# light_pcb.net
KiCad netlist of a schematic drawn in EAGLE
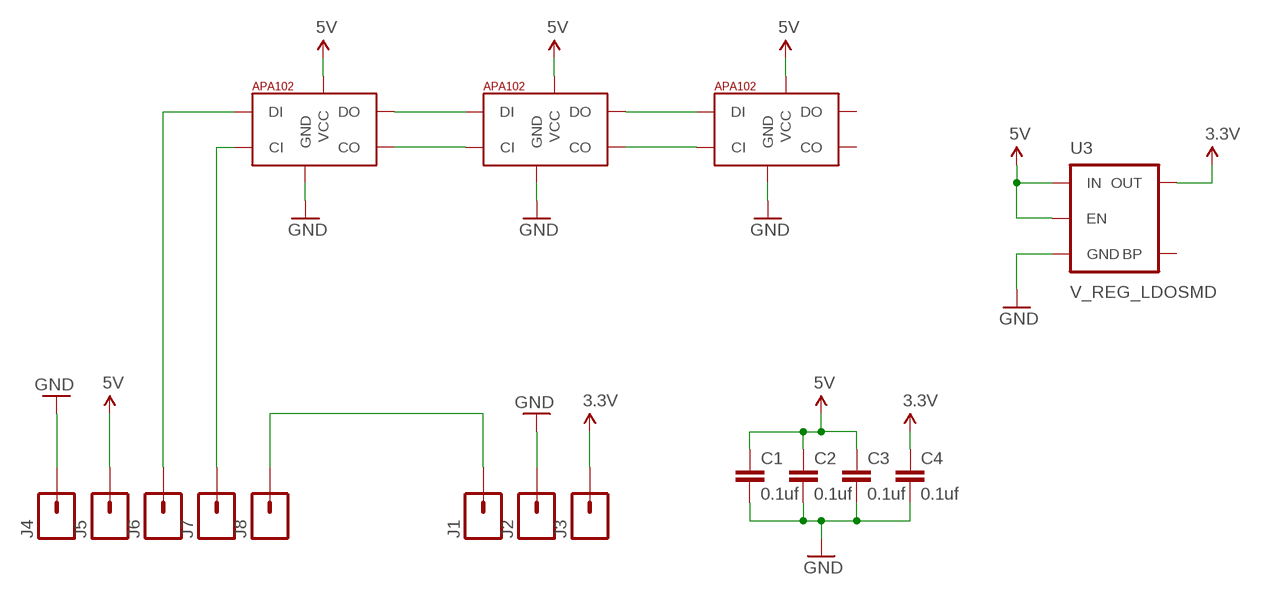
[diagram p0: schematic, sheet 1]

(export (version "E")
  (design (tool "Eeschema 10.0.6"))
  (components
    (comp (ref "C1")
      (value "0.1uf")
      (footprint "eagle-import:0805")
      (libsource (lib "eagle-import") (part "CAP0805"))
    )
    (comp (ref "C2")
      (value "0.1uf")
      (footprint "eagle-import:0805")
      (libsource (lib "eagle-import") (part "CAP0805"))
    )
    (comp (ref "C3")
      (value "0.1uf")
      (footprint "eagle-import:0805")
      (libsource (lib "eagle-import") (part "CAP0805"))
    )
    (comp (ref "C4")
      (value "0.1uf")
      (footprint "eagle-import:0805")
      (libsource (lib "eagle-import") (part "CAP0805"))
    )
    (comp (ref "J1")
      (value "M01SMD-4.5X1.5")
      (footprint "eagle-import:PAD-1.5X4.5")
      (libsource (lib "eagle-import") (part "M01SMD-4.5X1.5"))
    )
    (comp (ref "J2")
      (value "M01SMD-4.5X1.5")
      (footprint "eagle-import:PAD-1.5X4.5")
      (libsource (lib "eagle-import") (part "M01SMD-4.5X1.5"))
    )
    (comp (ref "J3")
      (value "M01SMD-4.5X1.5")
      (footprint "eagle-import:PAD-1.5X4.5")
      (libsource (lib "eagle-import") (part "M01SMD-4.5X1.5"))
    )
    (comp (ref "J4")
      (value "M01SMD-4.5X1.5")
      (footprint "eagle-import:PAD-1.5X4.5")
      (libsource (lib "eagle-import") (part "M01SMD-4.5X1.5"))
    )
    (comp (ref "J5")
      (value "M01SMD-4.5X1.5")
      (footprint "eagle-import:PAD-1.5X4.5")
      (libsource (lib "eagle-import") (part "M01SMD-4.5X1.5"))
    )
    (comp (ref "J6")
      (value "M01SMD-4.5X1.5")
      (footprint "eagle-import:PAD-1.5X4.5")
      (libsource (lib "eagle-import") (part "M01SMD-4.5X1.5"))
    )
    (comp (ref "J7")
      (value "M01SMD-4.5X1.5")
      (footprint "eagle-import:PAD-1.5X4.5")
      (libsource (lib "eagle-import") (part "M01SMD-4.5X1.5"))
    )
    (comp (ref "J8")
      (value "M01SMD-4.5X1.5")
      (footprint "eagle-import:PAD-1.5X4.5")
      (libsource (lib "eagle-import") (part "M01SMD-4.5X1.5"))
    )
    (comp (ref "U$1")
      (value "APA1025050")
      (footprint "eagle-import:APA102_5050")
      (libsource (lib "eagle-import") (part "APA1025050"))
    )
    (comp (ref "U$2")
      (value "APA1025050")
      (footprint "eagle-import:APA102_5050")
      (libsource (lib "eagle-import") (part "APA1025050"))
    )
    (comp (ref "U$3")
      (value "APA1025050")
      (footprint "eagle-import:APA102_5050")
      (libsource (lib "eagle-import") (part "APA1025050"))
    )
    (comp (ref "U3")
      (value "V_REG_LDOSMD")
      (footprint "eagle-import:SOT23-5")
      (libsource (lib "eagle-import") (part "V_REG_LDOSMD"))
    )
  )
  (nets
    (net (code "1") (name "3.3V") (class "Default")
      (node (ref "C4") (pin "1") (pinfunction "1_1") (pintype "passive"))
      (node (ref "J3") (pin "P$1") (pinfunction "1_P$1") (pintype "passive"))
      (node (ref "U3") (pin "5") (pinfunction "OUT_5") (pintype "passive"))
    )
    (net (code "2") (name "5V") (class "Default")
      (node (ref "C1") (pin "1") (pinfunction "1_1") (pintype "passive"))
      (node (ref "C2") (pin "1") (pinfunction "1_1") (pintype "passive"))
      (node (ref "C3") (pin "1") (pinfunction "1_1") (pintype "passive"))
      (node (ref "J5") (pin "P$1") (pinfunction "1_P$1") (pintype "passive"))
      (node (ref "U$1") (pin "1") (pinfunction "VCC_1") (pintype "bidirectional"))
      (node (ref "U$2") (pin "1") (pinfunction "VCC_1") (pintype "bidirectional"))
      (node (ref "U$3") (pin "1") (pinfunction "VCC_1") (pintype "bidirectional"))
      (node (ref "U3") (pin "1") (pinfunction "IN_1") (pintype "input"))
      (node (ref "U3") (pin "3") (pinfunction "EN_3") (pintype "input"))
    )
    (net (code "3") (name "GND") (class "Default")
      (node (ref "C1") (pin "2") (pinfunction "2_2") (pintype "passive"))
      (node (ref "C2") (pin "2") (pinfunction "2_2") (pintype "passive"))
      (node (ref "C3") (pin "2") (pinfunction "2_2") (pintype "passive"))
      (node (ref "C4") (pin "2") (pinfunction "2_2") (pintype "passive"))
      (node (ref "J2") (pin "P$1") (pinfunction "1_P$1") (pintype "passive"))
      (node (ref "J4") (pin "P$1") (pinfunction "1_P$1") (pintype "passive"))
      (node (ref "U$1") (pin "6") (pinfunction "GND_6") (pintype "bidirectional"))
      (node (ref "U$2") (pin "6") (pinfunction "GND_6") (pintype "bidirectional"))
      (node (ref "U$3") (pin "6") (pinfunction "GND_6") (pintype "bidirectional"))
      (node (ref "U3") (pin "2") (pinfunction "GND_2") (pintype "input"))
    )
    (net (code "4") (name "Net-(J1-1)") (class "Default")
      (node (ref "J1") (pin "P$1") (pinfunction "1_P$1") (pintype "passive"))
      (node (ref "J8") (pin "P$1") (pinfunction "1_P$1") (pintype "passive"))
    )
    (net (code "5") (name "Net-(J6-1)") (class "Default")
      (node (ref "J6") (pin "P$1") (pinfunction "1_P$1") (pintype "passive"))
      (node (ref "U$1") (pin "4") (pinfunction "DI_4") (pintype "bidirectional"))
    )
    (net (code "6") (name "Net-(J7-1)") (class "Default")
      (node (ref "J7") (pin "P$1") (pinfunction "1_P$1") (pintype "passive"))
      (node (ref "U$1") (pin "5") (pinfunction "CI_5") (pintype "bidirectional"))
    )
    (net (code "7") (name "Net-(U$1-CO)") (class "Default")
      (node (ref "U$1") (pin "2") (pinfunction "CO_2") (pintype "bidirectional"))
      (node (ref "U$2") (pin "5") (pinfunction "CI_5") (pintype "bidirectional"))
    )
    (net (code "8") (name "Net-(U$1-DO)") (class "Default")
      (node (ref "U$1") (pin "3") (pinfunction "DO_3") (pintype "bidirectional"))
      (node (ref "U$2") (pin "4") (pinfunction "DI_4") (pintype "bidirectional"))
    )
    (net (code "9") (name "Net-(U$2-CO)") (class "Default")
      (node (ref "U$2") (pin "2") (pinfunction "CO_2") (pintype "bidirectional"))
      (node (ref "U$3") (pin "5") (pinfunction "CI_5") (pintype "bidirectional"))
    )
    (net (code "10") (name "Net-(U$2-DO)") (class "Default")
      (node (ref "U$2") (pin "3") (pinfunction "DO_3") (pintype "bidirectional"))
      (node (ref "U$3") (pin "4") (pinfunction "DI_4") (pintype "bidirectional"))
    )
    (net (code "11") (name "unconnected-(U$3-CO-Pad2)") (class "Default")
      (node (ref "U$3") (pin "2") (pinfunction "CO_2") (pintype "bidirectional"))
    )
    (net (code "12") (name "unconnected-(U$3-DO-Pad3)") (class "Default")
      (node (ref "U$3") (pin "3") (pinfunction "DO_3") (pintype "bidirectional"))
    )
    (net (code "13") (name "unconnected-(U3-BP-Pad4)") (class "Default")
      (node (ref "U3") (pin "4") (pinfunction "BP_4") (pintype "input"))
    )
  )
)
